# Tag_V1.net
KiCad netlist of a schematic drawn in EAGLE
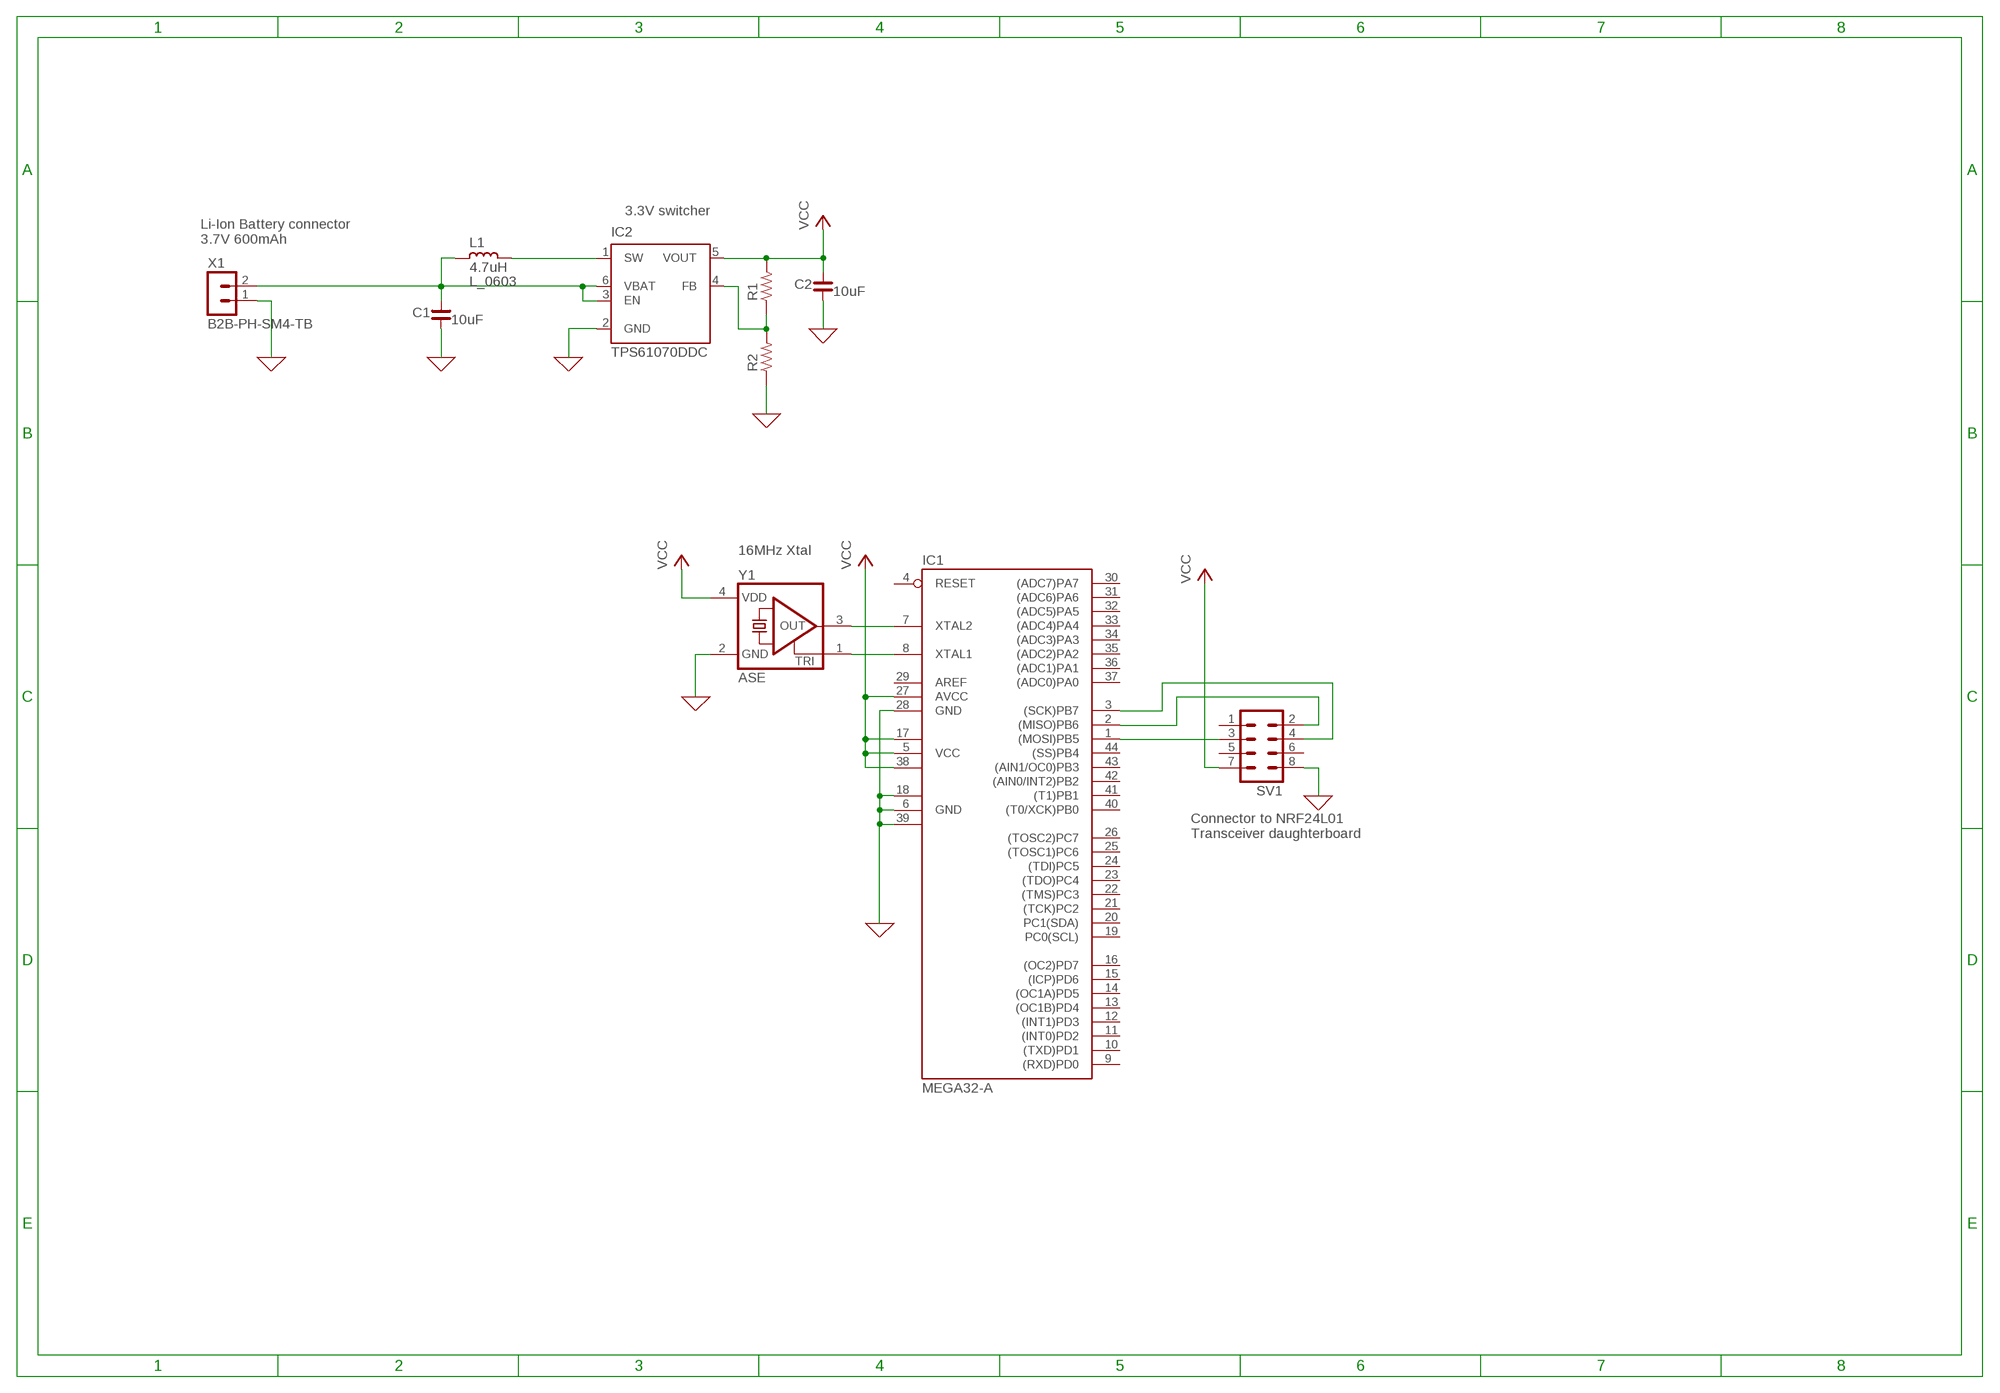
[diagram p0: schematic, sheet 1]

(export (version "E")
  (design (tool "Eeschema 10.0.6"))
  (components
    (comp (ref "C1")
      (value "C_0603")
      (footprint "eagle-import:C0603")
      (fields (field (name "C1") "10uF"))
      (libsource (lib "eagle-import") (part "C_0603"))
    )
    (comp (ref "C2")
      (value "C_0603")
      (footprint "eagle-import:C0603")
      (fields (field (name "C1") "10uF"))
      (libsource (lib "eagle-import") (part "C_0603"))
    )
    (comp (ref "IC1")
      (value "MEGA32-A")
      (footprint "eagle-import:TQFP44")
      (fields (field (name "MPN") "ATMEGA32-16AU"))
      (libsource (lib "eagle-import") (part "MEGA32-A"))
    )
    (comp (ref "IC2")
      (value "TPS61070DDC")
      (footprint "eagle-import:TSOT23-6_DDC")
      (fields (field (name "MPN") "TPS61070DDCR"))
      (libsource (lib "eagle-import") (part "TPS6107DDC0"))
    )
    (comp (ref "L1")
      (value "L_0603")
      (footprint "eagle-import:L0603")
      (fields (field (name "L1") "4.7uH"))
      (libsource (lib "eagle-import") (part "L_0603"))
    )
    (comp (ref "R1")
      (value "R_0603")
      (footprint "eagle-import:R0603")
      (libsource (lib "eagle-import") (part "R_0603"))
    )
    (comp (ref "R2")
      (value "R_0603")
      (footprint "eagle-import:R0603")
      (libsource (lib "eagle-import") (part "R_0603"))
    )
    (comp (ref "SV1")
      (value "MA04-2")
      (footprint "eagle-import:MA04-2")
      (libsource (lib "eagle-import") (part "MA04-2"))
    )
    (comp (ref "X1")
      (value "B2B-PH-SM4-TB")
      (footprint "eagle-import:B2B-PH-SM4-TB")
      (libsource (lib "eagle-import") (part "B2B-PH-SM4-TB"))
    )
    (comp (ref "Y1")
      (value "ASE")
      (footprint "eagle-import:ASE")
      (libsource (lib "eagle-import") (part "ASE"))
    )
  )
  (nets
    (net (code "1") (name "GND") (class "Default")
      (node (ref "C1") (pin "1") (pinfunction "1_1") (pintype "passive"))
      (node (ref "C2") (pin "1") (pinfunction "1_1") (pintype "passive"))
      (node (ref "IC1") (pin "18") (pinfunction "GND1_18") (pintype "power_in"))
      (node (ref "IC1") (pin "28") (pinfunction "GND_28") (pintype "power_in"))
      (node (ref "IC1") (pin "39") (pinfunction "GND2_39") (pintype "power_in"))
      (node (ref "IC1") (pin "6") (pinfunction "GND_6") (pintype "power_in"))
      (node (ref "IC2") (pin "2") (pinfunction "GND_2") (pintype "power_in"))
      (node (ref "R2") (pin "1") (pinfunction "1_1") (pintype "passive"))
      (node (ref "SV1") (pin "8") (pinfunction "8_8") (pintype "passive"))
      (node (ref "X1") (pin "1") (pinfunction "1_1") (pintype "passive"))
      (node (ref "Y1") (pin "2") (pinfunction "GND_2") (pintype "power_in"))
    )
    (net (code "2") (name "Net-(IC1-(MISO)PB6)") (class "Default")
      (node (ref "IC1") (pin "2") (pinfunction "(MISO)PB6_2") (pintype "bidirectional"))
      (node (ref "SV1") (pin "2") (pinfunction "2_2") (pintype "passive"))
    )
    (net (code "3") (name "Net-(IC1-(MOSI)PB5)") (class "Default")
      (node (ref "IC1") (pin "1") (pinfunction "(MOSI)PB5_1") (pintype "bidirectional"))
      (node (ref "SV1") (pin "3") (pinfunction "3_3") (pintype "passive"))
    )
    (net (code "4") (name "Net-(IC1-(SCK)PB7)") (class "Default")
      (node (ref "IC1") (pin "3") (pinfunction "(SCK)PB7_3") (pintype "bidirectional"))
      (node (ref "SV1") (pin "4") (pinfunction "4_4") (pintype "passive"))
    )
    (net (code "5") (name "Net-(IC1-XTAL1)") (class "Default")
      (node (ref "IC1") (pin "8") (pinfunction "XTAL1_8") (pintype "bidirectional"))
      (node (ref "Y1") (pin "1") (pinfunction "TRI_1") (pintype "input"))
    )
    (net (code "6") (name "Net-(IC1-XTAL2)") (class "Default")
      (node (ref "IC1") (pin "7") (pinfunction "XTAL2_7") (pintype "bidirectional"))
      (node (ref "Y1") (pin "3") (pinfunction "OUT_3") (pintype "output"))
    )
    (net (code "7") (name "Net-(IC2-EN)") (class "Default")
      (node (ref "C1") (pin "2") (pinfunction "2_2") (pintype "passive"))
      (node (ref "IC2") (pin "3") (pinfunction "EN_3") (pintype "input"))
      (node (ref "IC2") (pin "6") (pinfunction "VBAT_6") (pintype "input"))
      (node (ref "L1") (pin "2") (pinfunction "2_2") (pintype "passive"))
      (node (ref "X1") (pin "2") (pinfunction "2_2") (pintype "passive"))
    )
    (net (code "8") (name "Net-(IC2-FB)") (class "Default")
      (node (ref "IC2") (pin "4") (pinfunction "FB_4") (pintype "input"))
      (node (ref "R1") (pin "1") (pinfunction "1_1") (pintype "passive"))
      (node (ref "R2") (pin "2") (pinfunction "2_2") (pintype "passive"))
    )
    (net (code "9") (name "Net-(IC2-SW)") (class "Default")
      (node (ref "IC2") (pin "1") (pinfunction "SW_1") (pintype "input"))
      (node (ref "L1") (pin "1") (pinfunction "1_1") (pintype "passive"))
    )
    (net (code "10") (name "VCC") (class "Default")
      (node (ref "C2") (pin "2") (pinfunction "2_2") (pintype "passive"))
      (node (ref "IC1") (pin "17") (pinfunction "VCC1_17") (pintype "power_in"))
      (node (ref "IC1") (pin "27") (pinfunction "AVCC_27") (pintype "power_in"))
      (node (ref "IC1") (pin "38") (pinfunction "VCC2_38") (pintype "power_in"))
      (node (ref "IC1") (pin "5") (pinfunction "VCC_5") (pintype "power_in"))
      (node (ref "IC2") (pin "5") (pinfunction "VOUT_5") (pintype "passive"))
      (node (ref "R1") (pin "2") (pinfunction "2_2") (pintype "passive"))
      (node (ref "SV1") (pin "7") (pinfunction "7_7") (pintype "passive"))
      (node (ref "Y1") (pin "4") (pinfunction "VDD_4") (pintype "power_in"))
    )
    (net (code "11") (name "unconnected-(IC1-(ADC0)PA0-Pad37)") (class "Default")
      (node (ref "IC1") (pin "37") (pinfunction "(ADC0)PA0_37") (pintype "bidirectional"))
    )
    (net (code "12") (name "unconnected-(IC1-(ADC1)PA1-Pad36)") (class "Default")
      (node (ref "IC1") (pin "36") (pinfunction "(ADC1)PA1_36") (pintype "bidirectional"))
    )
    (net (code "13") (name "unconnected-(IC1-(ADC2)PA2-Pad35)") (class "Default")
      (node (ref "IC1") (pin "35") (pinfunction "(ADC2)PA2_35") (pintype "bidirectional"))
    )
    (net (code "14") (name "unconnected-(IC1-(ADC3)PA3-Pad34)") (class "Default")
      (node (ref "IC1") (pin "34") (pinfunction "(ADC3)PA3_34") (pintype "bidirectional"))
    )
    (net (code "15") (name "unconnected-(IC1-(ADC4)PA4-Pad33)") (class "Default")
      (node (ref "IC1") (pin "33") (pinfunction "(ADC4)PA4_33") (pintype "bidirectional"))
    )
    (net (code "16") (name "unconnected-(IC1-(ADC5)PA5-Pad32)") (class "Default")
      (node (ref "IC1") (pin "32") (pinfunction "(ADC5)PA5_32") (pintype "bidirectional"))
    )
    (net (code "17") (name "unconnected-(IC1-(ADC6)PA6-Pad31)") (class "Default")
      (node (ref "IC1") (pin "31") (pinfunction "(ADC6)PA6_31") (pintype "bidirectional"))
    )
    (net (code "18") (name "unconnected-(IC1-(ADC7)PA7-Pad30)") (class "Default")
      (node (ref "IC1") (pin "30") (pinfunction "(ADC7)PA7_30") (pintype "bidirectional"))
    )
    (net (code "19") (name "unconnected-(IC1-(AIN0{slash}INT2)PB2-Pad42)") (class "Default")
      (node (ref "IC1") (pin "42") (pinfunction "(AIN0/INT2)PB2_42") (pintype "bidirectional"))
    )
    (net (code "20") (name "unconnected-(IC1-(AIN1{slash}OC0)PB3-Pad43)") (class "Default")
      (node (ref "IC1") (pin "43") (pinfunction "(AIN1/OC0)PB3_43") (pintype "bidirectional"))
    )
    (net (code "21") (name "unconnected-(IC1-(ICP)PD6-Pad15)") (class "Default")
      (node (ref "IC1") (pin "15") (pinfunction "(ICP)PD6_15") (pintype "bidirectional"))
    )
    (net (code "22") (name "unconnected-(IC1-(INT0)PD2-Pad11)") (class "Default")
      (node (ref "IC1") (pin "11") (pinfunction "(INT0)PD2_11") (pintype "bidirectional"))
    )
    (net (code "23") (name "unconnected-(IC1-(INT1)PD3-Pad12)") (class "Default")
      (node (ref "IC1") (pin "12") (pinfunction "(INT1)PD3_12") (pintype "bidirectional"))
    )
    (net (code "24") (name "unconnected-(IC1-(OC1A)PD5-Pad14)") (class "Default")
      (node (ref "IC1") (pin "14") (pinfunction "(OC1A)PD5_14") (pintype "bidirectional"))
    )
    (net (code "25") (name "unconnected-(IC1-(OC1B)PD4-Pad13)") (class "Default")
      (node (ref "IC1") (pin "13") (pinfunction "(OC1B)PD4_13") (pintype "bidirectional"))
    )
    (net (code "26") (name "unconnected-(IC1-(OC2)PD7-Pad16)") (class "Default")
      (node (ref "IC1") (pin "16") (pinfunction "(OC2)PD7_16") (pintype "bidirectional"))
    )
    (net (code "27") (name "unconnected-(IC1-(RXD)PD0-Pad9)") (class "Default")
      (node (ref "IC1") (pin "9") (pinfunction "(RXD)PD0_9") (pintype "bidirectional"))
    )
    (net (code "28") (name "unconnected-(IC1-(SS)PB4-Pad44)") (class "Default")
      (node (ref "IC1") (pin "44") (pinfunction "(SS)PB4_44") (pintype "bidirectional"))
    )
    (net (code "29") (name "unconnected-(IC1-(T0{slash}XCK)PB0-Pad40)") (class "Default")
      (node (ref "IC1") (pin "40") (pinfunction "(T0/XCK)PB0_40") (pintype "bidirectional"))
    )
    (net (code "30") (name "unconnected-(IC1-(T1)PB1-Pad41)") (class "Default")
      (node (ref "IC1") (pin "41") (pinfunction "(T1)PB1_41") (pintype "bidirectional"))
    )
    (net (code "31") (name "unconnected-(IC1-(TCK)PC2-Pad21)") (class "Default")
      (node (ref "IC1") (pin "21") (pinfunction "(TCK)PC2_21") (pintype "bidirectional"))
    )
    (net (code "32") (name "unconnected-(IC1-(TDI)PC5-Pad24)") (class "Default")
      (node (ref "IC1") (pin "24") (pinfunction "(TDI)PC5_24") (pintype "bidirectional"))
    )
    (net (code "33") (name "unconnected-(IC1-(TDO)PC4-Pad23)") (class "Default")
      (node (ref "IC1") (pin "23") (pinfunction "(TDO)PC4_23") (pintype "bidirectional"))
    )
    (net (code "34") (name "unconnected-(IC1-(TMS)PC3-Pad22)") (class "Default")
      (node (ref "IC1") (pin "22") (pinfunction "(TMS)PC3_22") (pintype "bidirectional"))
    )
    (net (code "35") (name "unconnected-(IC1-(TOSC1)PC6-Pad25)") (class "Default")
      (node (ref "IC1") (pin "25") (pinfunction "(TOSC1)PC6_25") (pintype "bidirectional"))
    )
    (net (code "36") (name "unconnected-(IC1-(TOSC2)PC7-Pad26)") (class "Default")
      (node (ref "IC1") (pin "26") (pinfunction "(TOSC2)PC7_26") (pintype "bidirectional"))
    )
    (net (code "37") (name "unconnected-(IC1-(TXD)PD1-Pad10)") (class "Default")
      (node (ref "IC1") (pin "10") (pinfunction "(TXD)PD1_10") (pintype "bidirectional"))
    )
    (net (code "38") (name "unconnected-(IC1-AREF-Pad29)") (class "Default")
      (node (ref "IC1") (pin "29") (pinfunction "AREF_29") (pintype "passive"))
    )
    (net (code "39") (name "unconnected-(IC1-PC0(SCL)-Pad19)") (class "Default")
      (node (ref "IC1") (pin "19") (pinfunction "PC0(SCL)_19") (pintype "bidirectional"))
    )
    (net (code "40") (name "unconnected-(IC1-PC1(SDA)-Pad20)") (class "Default")
      (node (ref "IC1") (pin "20") (pinfunction "PC1(SDA)_20") (pintype "bidirectional"))
    )
    (net (code "41") (name "unconnected-(IC1-RESET-Pad4)") (class "Default")
      (node (ref "IC1") (pin "4") (pinfunction "RESET_4") (pintype "input"))
    )
    (net (code "42") (name "unconnected-(SV1-Pad1)") (class "Default")
      (node (ref "SV1") (pin "1") (pinfunction "1_1") (pintype "passive"))
    )
    (net (code "43") (name "unconnected-(SV1-Pad5)") (class "Default")
      (node (ref "SV1") (pin "5") (pinfunction "5_5") (pintype "passive"))
    )
    (net (code "44") (name "unconnected-(SV1-Pad6)") (class "Default")
      (node (ref "SV1") (pin "6") (pinfunction "6_6") (pintype "passive"))
    )
  )
)
